# Gameboy_Cartridge.net
KiCad netlist of a schematic drawn in EAGLE
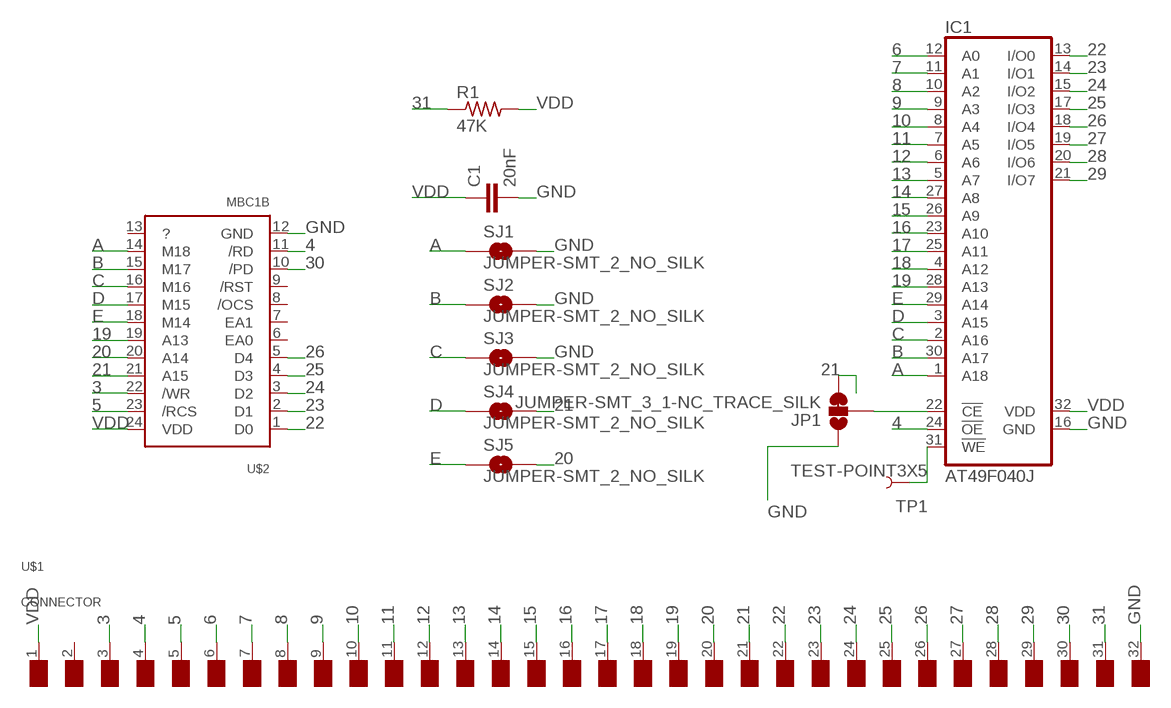
[diagram p0: schematic, sheet 1]

(export (version "E")
  (design (tool "Eeschema 10.0.6"))
  (components
    (comp (ref "C1")
      (value "20nF")
      (footprint "eagle-import:C0805")
      (libsource (lib "eagle-import") (part "C-EUC0805"))
    )
    (comp (ref "IC1")
      (value "AT49F040J")
      (footprint "eagle-import:PLCC32R")
      (libsource (lib "eagle-import") (part "AT49F040J"))
    )
    (comp (ref "JP1")
      (value "JUMPER-SMT_3_1-NC_TRACE_SILK")
      (footprint "eagle-import:SMT-JUMPER_3_1-NC_TRACE_SILK")
      (libsource (lib "eagle-import") (part "JUMPER-SMT_3_1-NC_TRACE_SILK"))
    )
    (comp (ref "R1")
      (value "47K")
      (footprint "eagle-import:M0805")
      (libsource (lib "eagle-import") (part "R-US_M0805"))
    )
    (comp (ref "SJ1")
      (value "JUMPER-SMT_2_NO_SILK")
      (footprint "eagle-import:SMT-JUMPER_2_NO_SILK")
      (libsource (lib "eagle-import") (part "JUMPER-SMT_2_NO_SILK"))
    )
    (comp (ref "SJ2")
      (value "JUMPER-SMT_2_NO_SILK")
      (footprint "eagle-import:SMT-JUMPER_2_NO_SILK")
      (libsource (lib "eagle-import") (part "JUMPER-SMT_2_NO_SILK"))
    )
    (comp (ref "SJ3")
      (value "JUMPER-SMT_2_NO_SILK")
      (footprint "eagle-import:SMT-JUMPER_2_NO_SILK")
      (libsource (lib "eagle-import") (part "JUMPER-SMT_2_NO_SILK"))
    )
    (comp (ref "SJ4")
      (value "JUMPER-SMT_2_NO_SILK")
      (footprint "eagle-import:SMT-JUMPER_2_NO_SILK")
      (libsource (lib "eagle-import") (part "JUMPER-SMT_2_NO_SILK"))
    )
    (comp (ref "SJ5")
      (value "JUMPER-SMT_2_NO_SILK")
      (footprint "eagle-import:SMT-JUMPER_2_NO_SILK")
      (libsource (lib "eagle-import") (part "JUMPER-SMT_2_NO_SILK"))
    )
    (comp (ref "TP1")
      (value "TEST-POINT3X5")
      (footprint "eagle-import:PAD.03X.05")
      (libsource (lib "eagle-import") (part "TEST-POINT3X5"))
    )
    (comp (ref "U$1")
      (value "CONNECTOR")
      (footprint "eagle-import:CONNECTOR")
      (libsource (lib "eagle-import") (part "CONNECTOR"))
    )
    (comp (ref "U$2")
      (value "MBC1B")
      (footprint "eagle-import:MBC1B")
      (libsource (lib "eagle-import") (part "MBC1B"))
    )
  )
  (nets
    (net (code "1") (name "/3") (class "Default")
      (node (ref "U$1") (pin "3") (pinfunction "/WR_3") (pintype "bidirectional"))
      (node (ref "U$2") (pin "22") (pinfunction "/WR_22") (pintype "bidirectional"))
    )
    (net (code "2") (name "/4") (class "Default")
      (node (ref "IC1") (pin "24") (pinfunction "~{OE}_24") (pintype "input"))
      (node (ref "U$1") (pin "4") (pinfunction "/RD_4") (pintype "bidirectional"))
      (node (ref "U$2") (pin "11") (pinfunction "/RD_11") (pintype "bidirectional"))
    )
    (net (code "3") (name "/5") (class "Default")
      (node (ref "U$1") (pin "5") (pinfunction "/RCS_5") (pintype "bidirectional"))
      (node (ref "U$2") (pin "23") (pinfunction "/RCS_23") (pintype "bidirectional"))
    )
    (net (code "4") (name "/6") (class "Default")
      (node (ref "IC1") (pin "12") (pinfunction "A0_12") (pintype "input"))
      (node (ref "U$1") (pin "6") (pinfunction "A0_6") (pintype "bidirectional"))
    )
    (net (code "5") (name "/7") (class "Default")
      (node (ref "IC1") (pin "11") (pinfunction "A1_11") (pintype "input"))
      (node (ref "U$1") (pin "7") (pinfunction "A1_7") (pintype "bidirectional"))
    )
    (net (code "6") (name "/8") (class "Default")
      (node (ref "IC1") (pin "10") (pinfunction "A2_10") (pintype "input"))
      (node (ref "U$1") (pin "8") (pinfunction "A2_8") (pintype "bidirectional"))
    )
    (net (code "7") (name "/9") (class "Default")
      (node (ref "IC1") (pin "9") (pinfunction "A3_9") (pintype "input"))
      (node (ref "U$1") (pin "9") (pinfunction "A3_9") (pintype "bidirectional"))
    )
    (net (code "8") (name "/10") (class "Default")
      (node (ref "IC1") (pin "8") (pinfunction "A4_8") (pintype "input"))
      (node (ref "U$1") (pin "10") (pinfunction "A4_10") (pintype "bidirectional"))
    )
    (net (code "9") (name "/11") (class "Default")
      (node (ref "IC1") (pin "7") (pinfunction "A5_7") (pintype "input"))
      (node (ref "U$1") (pin "11") (pinfunction "A5_11") (pintype "bidirectional"))
    )
    (net (code "10") (name "/12") (class "Default")
      (node (ref "IC1") (pin "6") (pinfunction "A6_6") (pintype "input"))
      (node (ref "U$1") (pin "12") (pinfunction "A6_12") (pintype "bidirectional"))
    )
    (net (code "11") (name "/13") (class "Default")
      (node (ref "IC1") (pin "5") (pinfunction "A7_5") (pintype "input"))
      (node (ref "U$1") (pin "13") (pinfunction "A7_13") (pintype "bidirectional"))
    )
    (net (code "12") (name "/14") (class "Default")
      (node (ref "IC1") (pin "27") (pinfunction "A8_27") (pintype "input"))
      (node (ref "U$1") (pin "14") (pinfunction "A8_14") (pintype "bidirectional"))
    )
    (net (code "13") (name "/15") (class "Default")
      (node (ref "IC1") (pin "26") (pinfunction "A9_26") (pintype "input"))
      (node (ref "U$1") (pin "15") (pinfunction "A9_15") (pintype "bidirectional"))
    )
    (net (code "14") (name "/16") (class "Default")
      (node (ref "IC1") (pin "23") (pinfunction "A10_23") (pintype "input"))
      (node (ref "U$1") (pin "16") (pinfunction "A10_16") (pintype "bidirectional"))
    )
    (net (code "15") (name "/17") (class "Default")
      (node (ref "IC1") (pin "25") (pinfunction "A11_25") (pintype "input"))
      (node (ref "U$1") (pin "17") (pinfunction "A11_17") (pintype "bidirectional"))
    )
    (net (code "16") (name "/18") (class "Default")
      (node (ref "IC1") (pin "4") (pinfunction "A12_4") (pintype "input"))
      (node (ref "U$1") (pin "18") (pinfunction "A12_18") (pintype "bidirectional"))
    )
    (net (code "17") (name "/19") (class "Default")
      (node (ref "IC1") (pin "28") (pinfunction "A13_28") (pintype "input"))
      (node (ref "U$1") (pin "19") (pinfunction "A13_19") (pintype "bidirectional"))
      (node (ref "U$2") (pin "19") (pinfunction "A13_19") (pintype "bidirectional"))
    )
    (net (code "18") (name "/20") (class "Default")
      (node (ref "SJ5") (pin "2") (pinfunction "2_2") (pintype "passive"))
      (node (ref "U$1") (pin "20") (pinfunction "A14_20") (pintype "bidirectional"))
      (node (ref "U$2") (pin "20") (pinfunction "A14_20") (pintype "bidirectional"))
    )
    (net (code "19") (name "/21") (class "Default")
      (node (ref "JP1") (pin "3") (pinfunction "3_3") (pintype "passive"))
      (node (ref "SJ4") (pin "2") (pinfunction "2_2") (pintype "passive"))
      (node (ref "U$1") (pin "21") (pinfunction "A15_21") (pintype "bidirectional"))
      (node (ref "U$2") (pin "21") (pinfunction "A15_21") (pintype "bidirectional"))
    )
    (net (code "20") (name "/22") (class "Default")
      (node (ref "IC1") (pin "13") (pinfunction "I/O0_13") (pintype "tri_state"))
      (node (ref "U$1") (pin "22") (pinfunction "D0_22") (pintype "bidirectional"))
      (node (ref "U$2") (pin "1") (pinfunction "D0_1") (pintype "bidirectional"))
    )
    (net (code "21") (name "/23") (class "Default")
      (node (ref "IC1") (pin "14") (pinfunction "I/O1_14") (pintype "tri_state"))
      (node (ref "U$1") (pin "23") (pinfunction "D1_23") (pintype "bidirectional"))
      (node (ref "U$2") (pin "2") (pinfunction "D1_2") (pintype "bidirectional"))
    )
    (net (code "22") (name "/24") (class "Default")
      (node (ref "IC1") (pin "15") (pinfunction "I/O2_15") (pintype "tri_state"))
      (node (ref "U$1") (pin "24") (pinfunction "D2_24") (pintype "bidirectional"))
      (node (ref "U$2") (pin "3") (pinfunction "D2_3") (pintype "bidirectional"))
    )
    (net (code "23") (name "/25") (class "Default")
      (node (ref "IC1") (pin "17") (pinfunction "I/O3_17") (pintype "tri_state"))
      (node (ref "U$1") (pin "25") (pinfunction "D3_25") (pintype "bidirectional"))
      (node (ref "U$2") (pin "4") (pinfunction "D3_4") (pintype "bidirectional"))
    )
    (net (code "24") (name "/26") (class "Default")
      (node (ref "IC1") (pin "18") (pinfunction "I/O4_18") (pintype "tri_state"))
      (node (ref "U$1") (pin "26") (pinfunction "D4_26") (pintype "bidirectional"))
      (node (ref "U$2") (pin "5") (pinfunction "D4_5") (pintype "bidirectional"))
    )
    (net (code "25") (name "/27") (class "Default")
      (node (ref "IC1") (pin "19") (pinfunction "I/O5_19") (pintype "tri_state"))
      (node (ref "U$1") (pin "27") (pinfunction "D5_27") (pintype "bidirectional"))
    )
    (net (code "26") (name "/28") (class "Default")
      (node (ref "IC1") (pin "20") (pinfunction "I/O6_20") (pintype "tri_state"))
      (node (ref "U$1") (pin "28") (pinfunction "D6_28") (pintype "bidirectional"))
    )
    (net (code "27") (name "/29") (class "Default")
      (node (ref "IC1") (pin "21") (pinfunction "I/O7_21") (pintype "tri_state"))
      (node (ref "U$1") (pin "29") (pinfunction "D7_29") (pintype "bidirectional"))
    )
    (net (code "28") (name "/30") (class "Default")
      (node (ref "U$1") (pin "30") (pinfunction "/RS_30") (pintype "bidirectional"))
      (node (ref "U$2") (pin "10") (pinfunction "/PD_10") (pintype "bidirectional"))
    )
    (net (code "29") (name "/31") (class "Default")
      (node (ref "R1") (pin "1") (pinfunction "1_1") (pintype "passive"))
      (node (ref "U$1") (pin "31") (pinfunction "VIN_31") (pintype "bidirectional"))
    )
    (net (code "30") (name "/A") (class "Default")
      (node (ref "IC1") (pin "1") (pinfunction "A18_1") (pintype "input"))
      (node (ref "SJ1") (pin "1") (pinfunction "1_1") (pintype "passive"))
      (node (ref "U$2") (pin "14") (pinfunction "M18_14") (pintype "bidirectional"))
    )
    (net (code "31") (name "/B") (class "Default")
      (node (ref "IC1") (pin "30") (pinfunction "A17_30") (pintype "input"))
      (node (ref "SJ2") (pin "1") (pinfunction "1_1") (pintype "passive"))
      (node (ref "U$2") (pin "15") (pinfunction "M17_15") (pintype "bidirectional"))
    )
    (net (code "32") (name "/C") (class "Default")
      (node (ref "IC1") (pin "2") (pinfunction "A16_2") (pintype "input"))
      (node (ref "SJ3") (pin "1") (pinfunction "1_1") (pintype "passive"))
      (node (ref "U$2") (pin "16") (pinfunction "M16_16") (pintype "bidirectional"))
    )
    (net (code "33") (name "/D") (class "Default")
      (node (ref "IC1") (pin "3") (pinfunction "A15_3") (pintype "input"))
      (node (ref "SJ4") (pin "1") (pinfunction "1_1") (pintype "passive"))
      (node (ref "U$2") (pin "17") (pinfunction "M15_17") (pintype "bidirectional"))
    )
    (net (code "34") (name "/E") (class "Default")
      (node (ref "IC1") (pin "29") (pinfunction "A14_29") (pintype "input"))
      (node (ref "SJ5") (pin "1") (pinfunction "1_1") (pintype "passive"))
      (node (ref "U$2") (pin "18") (pinfunction "M14_18") (pintype "bidirectional"))
    )
    (net (code "35") (name "/GND") (class "Default")
      (node (ref "C1") (pin "2") (pinfunction "2_2") (pintype "passive"))
      (node (ref "IC1") (pin "16") (pinfunction "GND_16") (pintype "power_in"))
      (node (ref "JP1") (pin "1") (pinfunction "1_1") (pintype "passive"))
      (node (ref "SJ1") (pin "2") (pinfunction "2_2") (pintype "passive"))
      (node (ref "SJ2") (pin "2") (pinfunction "2_2") (pintype "passive"))
      (node (ref "SJ3") (pin "2") (pinfunction "2_2") (pintype "passive"))
      (node (ref "U$1") (pin "32") (pinfunction "GND_32") (pintype "power_in"))
      (node (ref "U$2") (pin "12") (pinfunction "GND_12") (pintype "power_in"))
    )
    (net (code "36") (name "/VDD") (class "Default")
      (node (ref "C1") (pin "1") (pinfunction "1_1") (pintype "passive"))
      (node (ref "IC1") (pin "32") (pinfunction "VDD_32") (pintype "power_in"))
      (node (ref "R1") (pin "2") (pinfunction "2_2") (pintype "passive"))
      (node (ref "U$1") (pin "1") (pinfunction "VDD_1") (pintype "power_in"))
      (node (ref "U$2") (pin "24") (pinfunction "VDD_24") (pintype "power_in"))
    )
    (net (code "37") (name "Net-(IC1-~{CE})") (class "Default")
      (node (ref "IC1") (pin "22") (pinfunction "~{CE}_22") (pintype "input"))
      (node (ref "JP1") (pin "2") (pinfunction "2_2") (pintype "passive"))
    )
    (net (code "38") (name "Net-(IC1-~{WE})") (class "Default")
      (node (ref "IC1") (pin "31") (pinfunction "~{WE}_31") (pintype "input"))
      (node (ref "TP1") (pin "P$1") (pinfunction "1_P$1") (pintype "bidirectional"))
    )
    (net (code "39") (name "unconnected-(U$1-NC-Pad2)") (class "Default")
      (node (ref "U$1") (pin "2") (pinfunction "NC_2") (pintype "no_connect"))
    )
    (net (code "40") (name "unconnected-(U$2-?-Pad13)") (class "Default")
      (node (ref "U$2") (pin "13") (pinfunction "?_13") (pintype "bidirectional"))
    )
    (net (code "41") (name "unconnected-(U$2-EA0-Pad6)") (class "Default")
      (node (ref "U$2") (pin "6") (pinfunction "EA0_6") (pintype "bidirectional"))
    )
    (net (code "42") (name "unconnected-(U$2-EA1-Pad7)") (class "Default")
      (node (ref "U$2") (pin "7") (pinfunction "EA1_7") (pintype "bidirectional"))
    )
    (net (code "43") (name "unconnected-(U$2-{slash}OCS-Pad8)") (class "Default")
      (node (ref "U$2") (pin "8") (pinfunction "/OCS_8") (pintype "bidirectional"))
    )
    (net (code "44") (name "unconnected-(U$2-{slash}RST-Pad9)") (class "Default")
      (node (ref "U$2") (pin "9") (pinfunction "/RST_9") (pintype "bidirectional"))
    )
  )
)
